# RP2350_MCU.net
KiCad netlist of a schematic drawn in Altium Designer
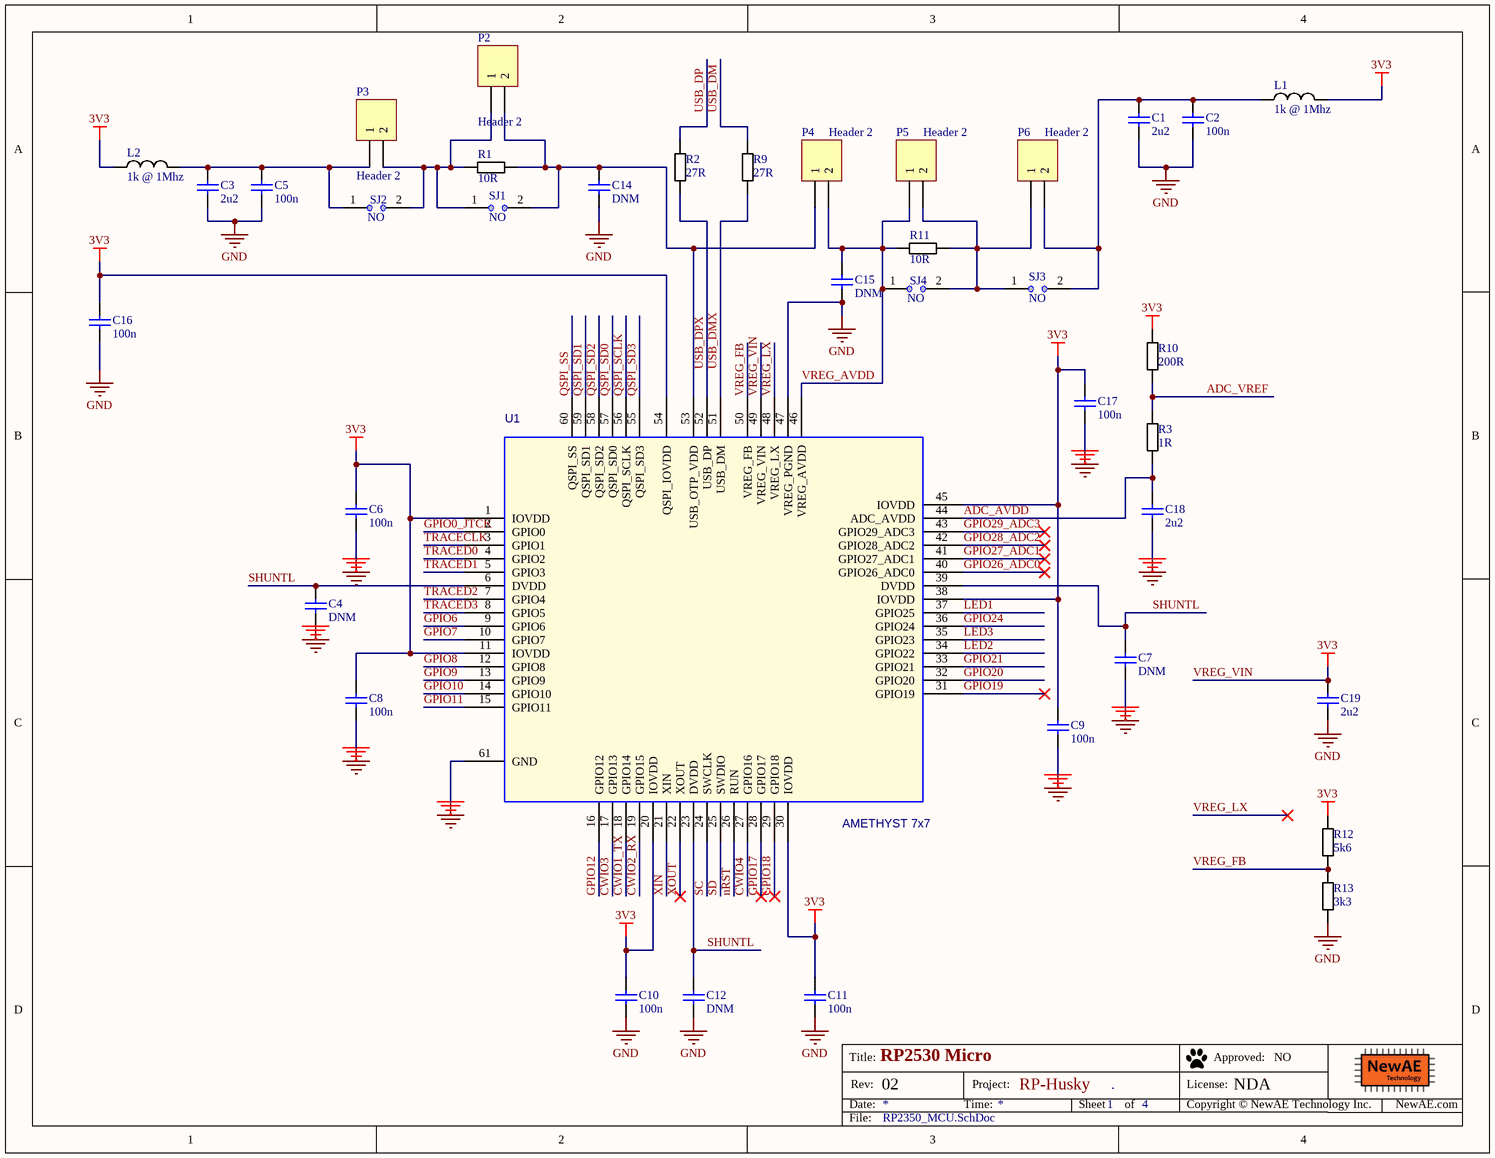
[diagram p0: RP2350_MCU.SchDoc]

(export (version "E")
  (design (tool "Eeschema 10.0.6"))
  (components
    (comp (ref "C1")
      (value "2u2")
      (footprint "CAPC0603_M")
      (description "2u2, 0603")
      (fields (field (name "PART NUMBER") "CCHIP-2u2-0603"))
      (libsource (lib "NewAE_AltiumLib") (part "CAP"))
    )
    (comp (ref "C2")
      (value "100n")
      (footprint "CAPC0402_M")
      (description "100n, 0402")
      (fields (field (name "PART NUMBER") "CCHIP-100n-0402"))
      (libsource (lib "NewAE_AltiumLib") (part "CAP"))
    )
    (comp (ref "C3")
      (value "2u2")
      (footprint "CAPC0603_M")
      (description "2u2, 0603")
      (fields (field (name "PART NUMBER") "CCHIP-2u2-0603"))
      (libsource (lib "NewAE_AltiumLib") (part "CAP"))
    )
    (comp (ref "C4")
      (value "DNM")
      (footprint "CAPC0603_M")
      (description "DNM, 0603")
      (fields (field (name "PART NUMBER") "CCHIP-DNM-0603"))
      (libsource (lib "NewAE_AltiumLib") (part "CAP"))
    )
    (comp (ref "C5")
      (value "100n")
      (footprint "CAPC0402_M")
      (description "100n, 0402")
      (fields (field (name "PART NUMBER") "CCHIP-100n-0402"))
      (libsource (lib "NewAE_AltiumLib") (part "CAP"))
    )
    (comp (ref "C6")
      (value "100n")
      (footprint "CAPC0402_M")
      (description "100n, 0402")
      (fields (field (name "PART NUMBER") "CCHIP-100n-0402"))
      (libsource (lib "NewAE_AltiumLib") (part "CAP"))
    )
    (comp (ref "C7")
      (value "DNM")
      (footprint "CAPC0603_M")
      (description "DNM, 0603")
      (fields (field (name "PART NUMBER") "CCHIP-DNM-0603"))
      (libsource (lib "NewAE_AltiumLib") (part "CAP"))
    )
    (comp (ref "C8")
      (value "100n")
      (footprint "CAPC0402_M")
      (description "100n, 0402")
      (fields (field (name "PART NUMBER") "CCHIP-100n-0402"))
      (libsource (lib "NewAE_AltiumLib") (part "CAP"))
    )
    (comp (ref "C9")
      (value "100n")
      (footprint "CAPC0402_M")
      (description "100n, 0402")
      (fields (field (name "PART NUMBER") "CCHIP-100n-0402"))
      (libsource (lib "NewAE_AltiumLib") (part "CAP"))
    )
    (comp (ref "C10")
      (value "100n")
      (footprint "CAPC0402_M")
      (description "100n, 0402")
      (fields (field (name "PART NUMBER") "CCHIP-100n-0402"))
      (libsource (lib "NewAE_AltiumLib") (part "CAP"))
    )
    (comp (ref "C11")
      (value "100n")
      (footprint "CAPC0402_M")
      (description "100n, 0402")
      (fields (field (name "PART NUMBER") "CCHIP-100n-0402"))
      (libsource (lib "NewAE_AltiumLib") (part "CAP"))
    )
    (comp (ref "C12")
      (value "DNM")
      (footprint "CAPC0603_M")
      (description "DNM, 0603")
      (fields (field (name "PART NUMBER") "CCHIP-DNM-0603"))
      (libsource (lib "NewAE_AltiumLib") (part "CAP"))
    )
    (comp (ref "C14")
      (value "DNM")
      (footprint "CAPC0603_M")
      (description "DNM, 0603")
      (fields (field (name "PART NUMBER") "CCHIP-DNM-0603"))
      (libsource (lib "NewAE_AltiumLib") (part "CAP"))
    )
    (comp (ref "C15")
      (value "DNM")
      (footprint "CAPC0603_M")
      (description "DNM, 0603")
      (fields (field (name "PART NUMBER") "CCHIP-DNM-0603"))
      (libsource (lib "NewAE_AltiumLib") (part "CAP"))
    )
    (comp (ref "C16")
      (value "100n")
      (footprint "CAPC0402_M")
      (description "100n, 0402")
      (fields (field (name "PART NUMBER") "CCHIP-100n-0402"))
      (libsource (lib "NewAE_AltiumLib") (part "CAP"))
    )
    (comp (ref "C17")
      (value "100n")
      (footprint "CAPC0402_M")
      (description "100n, 0402")
      (fields (field (name "PART NUMBER") "CCHIP-100n-0402"))
      (libsource (lib "NewAE_AltiumLib") (part "CAP"))
    )
    (comp (ref "C18")
      (value "2u2")
      (footprint "CAPC0603_M")
      (description "2u2, 0603")
      (fields (field (name "PART NUMBER") "CCHIP-2u2-0603"))
      (libsource (lib "NewAE_AltiumLib") (part "CAP"))
    )
    (comp (ref "C19")
      (value "2u2")
      (footprint "CAPC0603_M")
      (description "2u2, 0603")
      (fields (field (name "PART NUMBER") "CCHIP-2u2-0603"))
      (libsource (lib "NewAE_AltiumLib") (part "CAP"))
    )
    (comp (ref "L1")
      (value "1k @ 1Mhz")
      (footprint "IND_0603")
      (description "Ferrite Beads HI CUR CHIP BD 0603 1000OHMS 25%")
      (fields (field (name "PART NUMBER") "FBCHIP-1k-0603"))
      (libsource (lib "NewAE_AltiumLib") (part "IND"))
    )
    (comp (ref "L2")
      (value "1k @ 1Mhz")
      (footprint "IND_0603")
      (description "Ferrite Beads HI CUR CHIP BD 0603 1000OHMS 25%")
      (fields (field (name "PART NUMBER") "FBCHIP-1k-0603"))
      (libsource (lib "NewAE_AltiumLib") (part "IND"))
    )
    (comp (ref "P2")
      (value "Header 2")
      (footprint "HDR1X2")
      (description "Header, 2-Pin")
      (fields (field (name "PUBLISHER") "Altium Limited"))
      (libsource (lib "Miscellaneous Connectors") (part "Header 2"))
    )
    (comp (ref "P3")
      (value "Header 2")
      (footprint "HDR1X2")
      (description "Header, 2-Pin")
      (fields (field (name "PUBLISHER") "Altium Limited"))
      (libsource (lib "Miscellaneous Connectors") (part "Header 2"))
    )
    (comp (ref "P4")
      (value "Header 2")
      (footprint "HDR1X2")
      (description "Header, 2-Pin")
      (fields (field (name "PUBLISHER") "Altium Limited"))
      (libsource (lib "Miscellaneous Connectors") (part "Header 2"))
    )
    (comp (ref "P5")
      (value "Header 2")
      (footprint "HDR1X2")
      (description "Header, 2-Pin")
      (fields (field (name "PUBLISHER") "Altium Limited"))
      (libsource (lib "Miscellaneous Connectors") (part "Header 2"))
    )
    (comp (ref "P6")
      (value "Header 2")
      (footprint "HDR1X2")
      (description "Header, 2-Pin")
      (fields (field (name "PUBLISHER") "Altium Limited"))
      (libsource (lib "Miscellaneous Connectors") (part "Header 2"))
    )
    (comp (ref "R1")
      (value "10R")
      (footprint "RESC1608X55N")
      (description "10R res, 0603, 1%, 1/10W")
      (fields (field (name "PART NUMBER") "RCHIP-10R-0603") (field (name "TOLERANCE") "1%"))
      (libsource (lib "NewAE_AltiumLib") (part "RES-EU"))
    )
    (comp (ref "R2")
      (value "27R")
      (footprint "RESC1608X55N")
      (description "27R res, 0603, 1%, 1/10W")
      (fields (field (name "PART NUMBER") "RCHIP-27R-0603") (field (name "TOLERANCE") "1%"))
      (libsource (lib "") (part "RES-EU_1"))
    )
    (comp (ref "R3")
      (value "1R")
      (footprint "RESC1608X55N")
      (description "1R res, 0603, 1%, 1/10W")
      (fields (field (name "PART NUMBER") "RCHIP-10R-0603") (field (name "TOLERANCE") "1%"))
      (libsource (lib "") (part "RES-EU_1"))
    )
    (comp (ref "R9")
      (value "27R")
      (footprint "RESC1608X55N")
      (description "27R res, 0603, 1%, 1/10W")
      (fields (field (name "PART NUMBER") "RCHIP-27R-0603") (field (name "TOLERANCE") "1%"))
      (libsource (lib "") (part "RES-EU_1"))
    )
    (comp (ref "R10")
      (value "200R")
      (footprint "RESC1608X55N")
      (description "200R res, 0603, 1%, 1/10W")
      (fields (field (name "PART NUMBER") "RCHIP-200R-0603") (field (name "TOLERANCE") "1%"))
      (libsource (lib "") (part "RES-EU_2"))
    )
    (comp (ref "R11")
      (value "10R")
      (footprint "RESC1608X55N")
      (description "10R res, 0603, 1%, 1/10W")
      (fields (field (name "PART NUMBER") "RCHIP-10R-0603") (field (name "TOLERANCE") "1%"))
      (libsource (lib "NewAE_AltiumLib") (part "RES-EU"))
    )
    (comp (ref "R12")
      (value "5k6")
      (footprint "RESC1608X55N")
      (description "5k6 res, 0603, 1%, 1/10W")
      (fields (field (name "PART NUMBER") "RCHIP-5K6-0603") (field (name "TOLERANCE") "1%"))
      (libsource (lib "") (part "RES-EU_2"))
    )
    (comp (ref "R13")
      (value "3k3")
      (footprint "RESC1608X55N")
      (description "3k3 res, 0603, 1%, 1/10W")
      (fields (field (name "PART NUMBER") "RCHIP-3K3-0603") (field (name "TOLERANCE") "1%"))
      (libsource (lib "") (part "RES-EU_2"))
    )
    (comp (ref "SJ1")
      (value "NO")
      (footprint "SJ_2S_NO")
      (description "Solder Jumper, NO")
      (fields (field (name "PART NUMBER") "SJ_2S_NO"))
      (libsource (lib "NewAE_AltiumLib") (part "SJ_2S_NO"))
    )
    (comp (ref "SJ2")
      (value "NO")
      (footprint "SJ_2S_NO")
      (description "Solder Jumper, NO")
      (fields (field (name "PART NUMBER") "SJ_2S_NO"))
      (libsource (lib "NewAE_AltiumLib") (part "SJ_2S_NO"))
    )
    (comp (ref "SJ3")
      (value "NO")
      (footprint "SJ_2S_NO")
      (description "Solder Jumper, NO")
      (fields (field (name "PART NUMBER") "SJ_2S_NO"))
      (libsource (lib "NewAE_AltiumLib") (part "SJ_2S_NO"))
    )
    (comp (ref "SJ4")
      (value "NO")
      (footprint "SJ_2S_NO")
      (description "Solder Jumper, NO")
      (fields (field (name "PART NUMBER") "SJ_2S_NO"))
      (libsource (lib "NewAE_AltiumLib") (part "SJ_2S_NO"))
    )
    (comp (ref "U1")
      (value "AMETHYST 7x7")
      (footprint "QFN60P700X700X85_HS-61M")
      (libsource (lib "*") (part "RPI_AMETHYST-7X7"))
    )
  )
  (nets
    (net (code "1") (name "/ADC_AVDD") (class "Default")
      (node (ref "C18") (pin "1") (pinfunction "1_1") (pintype "passive"))
      (node (ref "R3") (pin "1") (pinfunction "1_1") (pintype "passive"))
      (node (ref "U1") (pin "44") (pinfunction "ADC_AVDD_44") (pintype "power_in"))
    )
    (net (code "2") (name "/ADC_VREF") (class "Default")
      (node (ref "R10") (pin "2") (pinfunction "2_2") (pintype "passive"))
      (node (ref "R3") (pin "2") (pinfunction "2_2") (pintype "passive"))
    )
    (net (code "3") (name "/CWIO1_TX") (class "Default")
      (node (ref "U1") (pin "18") (pinfunction "GPIO14_18") (pintype "passive"))
    )
    (net (code "4") (name "/CWIO2_RX") (class "Default")
      (node (ref "U1") (pin "19") (pinfunction "GPIO15_19") (pintype "passive"))
    )
    (net (code "5") (name "/CWIO3") (class "Default")
      (node (ref "U1") (pin "17") (pinfunction "GPIO13_17") (pintype "passive"))
    )
    (net (code "6") (name "/CWIO4") (class "Default")
      (node (ref "U1") (pin "27") (pinfunction "GPIO16_27") (pintype "passive"))
    )
    (net (code "7") (name "/GPIO0_JTCK") (class "Default")
      (node (ref "U1") (pin "2") (pinfunction "GPIO0_2") (pintype "passive"))
    )
    (net (code "8") (name "/GPIO6") (class "Default")
      (node (ref "U1") (pin "9") (pinfunction "GPIO6_9") (pintype "passive"))
    )
    (net (code "9") (name "/GPIO7") (class "Default")
      (node (ref "U1") (pin "10") (pinfunction "GPIO7_10") (pintype "passive"))
    )
    (net (code "10") (name "/GPIO8") (class "Default")
      (node (ref "U1") (pin "12") (pinfunction "GPIO8_12") (pintype "passive"))
    )
    (net (code "11") (name "/GPIO9") (class "Default")
      (node (ref "U1") (pin "13") (pinfunction "GPIO9_13") (pintype "passive"))
    )
    (net (code "12") (name "/GPIO10") (class "Default")
      (node (ref "U1") (pin "14") (pinfunction "GPIO10_14") (pintype "passive"))
    )
    (net (code "13") (name "/GPIO11") (class "Default")
      (node (ref "U1") (pin "15") (pinfunction "GPIO11_15") (pintype "passive"))
    )
    (net (code "14") (name "/GPIO12") (class "Default")
      (node (ref "U1") (pin "16") (pinfunction "GPIO12_16") (pintype "passive"))
    )
    (net (code "15") (name "/GPIO17") (class "Default")
      (node (ref "U1") (pin "28") (pinfunction "GPIO17_28") (pintype "passive+no_connect"))
    )
    (net (code "16") (name "/GPIO18") (class "Default")
      (node (ref "U1") (pin "29") (pinfunction "GPIO18_29") (pintype "passive+no_connect"))
    )
    (net (code "17") (name "/GPIO19") (class "Default")
      (node (ref "U1") (pin "31") (pinfunction "GPIO19_31") (pintype "passive+no_connect"))
    )
    (net (code "18") (name "/GPIO20") (class "Default")
      (node (ref "U1") (pin "32") (pinfunction "GPIO20_32") (pintype "passive"))
    )
    (net (code "19") (name "/GPIO21") (class "Default")
      (node (ref "U1") (pin "33") (pinfunction "GPIO21_33") (pintype "passive"))
    )
    (net (code "20") (name "/GPIO24") (class "Default")
      (node (ref "U1") (pin "36") (pinfunction "GPIO24_36") (pintype "passive"))
    )
    (net (code "21") (name "/GPIO26_ADC0") (class "Default")
      (node (ref "U1") (pin "40") (pinfunction "GPIO26_ADC0_40") (pintype "passive+no_connect"))
    )
    (net (code "22") (name "/GPIO27_ADC1") (class "Default")
      (node (ref "U1") (pin "41") (pinfunction "GPIO27_ADC1_41") (pintype "passive+no_connect"))
    )
    (net (code "23") (name "/GPIO28_ADC2") (class "Default")
      (node (ref "U1") (pin "42") (pinfunction "GPIO28_ADC2_42") (pintype "passive+no_connect"))
    )
    (net (code "24") (name "/GPIO29_ADC3") (class "Default")
      (node (ref "U1") (pin "43") (pinfunction "GPIO29_ADC3_43") (pintype "passive+no_connect"))
    )
    (net (code "25") (name "/LED1") (class "Default")
      (node (ref "U1") (pin "37") (pinfunction "GPIO25_37") (pintype "passive"))
    )
    (net (code "26") (name "/LED2") (class "Default")
      (node (ref "U1") (pin "34") (pinfunction "GPIO22_34") (pintype "passive"))
    )
    (net (code "27") (name "/LED3") (class "Default")
      (node (ref "U1") (pin "35") (pinfunction "GPIO23_35") (pintype "passive"))
    )
    (net (code "28") (name "/QSPI_SCLK") (class "Default")
      (node (ref "U1") (pin "56") (pinfunction "QSPI_SCLK_56") (pintype "passive"))
    )
    (net (code "29") (name "/QSPI_SD0") (class "Default")
      (node (ref "U1") (pin "57") (pinfunction "QSPI_SD0_57") (pintype "passive"))
    )
    (net (code "30") (name "/QSPI_SD1") (class "Default")
      (node (ref "U1") (pin "59") (pinfunction "QSPI_SD1_59") (pintype "passive"))
    )
    (net (code "31") (name "/QSPI_SD2") (class "Default")
      (node (ref "U1") (pin "58") (pinfunction "QSPI_SD2_58") (pintype "passive"))
    )
    (net (code "32") (name "/QSPI_SD3") (class "Default")
      (node (ref "U1") (pin "55") (pinfunction "QSPI_SD3_55") (pintype "passive"))
    )
    (net (code "33") (name "/QSPI_SS") (class "Default")
      (node (ref "U1") (pin "60") (pinfunction "QSPI_SS_60") (pintype "passive"))
    )
    (net (code "34") (name "/SC") (class "Default")
      (node (ref "U1") (pin "24") (pinfunction "SWCLK_24") (pintype "passive"))
    )
    (net (code "35") (name "/SD") (class "Default")
      (node (ref "U1") (pin "25") (pinfunction "SWDIO_25") (pintype "passive"))
    )
    (net (code "36") (name "/SHUNTL") (class "Default")
      (node (ref "C12") (pin "1") (pinfunction "1_1") (pintype "passive"))
      (node (ref "C4") (pin "1") (pinfunction "1_1") (pintype "passive"))
      (node (ref "C7") (pin "1") (pinfunction "1_1") (pintype "passive"))
      (node (ref "U1") (pin "23") (pinfunction "DVDD_23") (pintype "power_in"))
      (node (ref "U1") (pin "39") (pinfunction "DVDD_39") (pintype "power_in"))
      (node (ref "U1") (pin "6") (pinfunction "DVDD_6") (pintype "power_in"))
    )
    (net (code "37") (name "/TRACECLK") (class "Default")
      (node (ref "U1") (pin "3") (pinfunction "GPIO1_3") (pintype "passive"))
    )
    (net (code "38") (name "/TRACED0") (class "Default")
      (node (ref "U1") (pin "4") (pinfunction "GPIO2_4") (pintype "passive"))
    )
    (net (code "39") (name "/TRACED1") (class "Default")
      (node (ref "U1") (pin "5") (pinfunction "GPIO3_5") (pintype "passive"))
    )
    (net (code "40") (name "/TRACED2") (class "Default")
      (node (ref "U1") (pin "7") (pinfunction "GPIO4_7") (pintype "passive"))
    )
    (net (code "41") (name "/TRACED3") (class "Default")
      (node (ref "U1") (pin "8") (pinfunction "GPIO5_8") (pintype "passive"))
    )
    (net (code "42") (name "/USB_DM") (class "Default")
      (node (ref "R9") (pin "2") (pinfunction "2_2") (pintype "passive"))
    )
    (net (code "43") (name "/USB_DMX") (class "Default")
      (node (ref "R9") (pin "1") (pinfunction "1_1") (pintype "passive"))
      (node (ref "U1") (pin "51") (pinfunction "USB_DM_51") (pintype "passive"))
    )
    (net (code "44") (name "/USB_DP") (class "Default")
      (node (ref "R2") (pin "2") (pinfunction "2_2") (pintype "passive"))
    )
    (net (code "45") (name "/USB_DPX") (class "Default")
      (node (ref "R2") (pin "1") (pinfunction "1_1") (pintype "passive"))
      (node (ref "U1") (pin "52") (pinfunction "USB_DP_52") (pintype "passive"))
    )
    (net (code "46") (name "/VREG_AVDD") (class "Default")
      (node (ref "C15") (pin "1") (pinfunction "1_1") (pintype "passive"))
      (node (ref "P4") (pin "2") (pinfunction "2_2") (pintype "passive"))
      (node (ref "P5") (pin "1") (pinfunction "1_1") (pintype "passive"))
      (node (ref "R11") (pin "1") (pinfunction "1_1") (pintype "passive"))
      (node (ref "SJ4") (pin "1") (pinfunction "1_1") (pintype "passive"))
      (node (ref "U1") (pin "46") (pinfunction "VREG_AVDD_46") (pintype "power_in"))
    )
    (net (code "47") (name "/VREG_FB") (class "Default")
      (node (ref "R12") (pin "2") (pinfunction "2_2") (pintype "passive"))
      (node (ref "R13") (pin "1") (pinfunction "1_1") (pintype "passive"))
      (node (ref "U1") (pin "50") (pinfunction "VREG_FB_50") (pintype "passive"))
    )
    (net (code "48") (name "/VREG_LX") (class "Default")
      (node (ref "U1") (pin "48") (pinfunction "VREG_LX_48") (pintype "passive+no_connect"))
    )
    (net (code "49") (name "/XIN") (class "Default")
      (node (ref "U1") (pin "21") (pinfunction "XIN_21") (pintype "passive"))
    )
    (net (code "50") (name "/XOUT") (class "Default")
      (node (ref "U1") (pin "22") (pinfunction "XOUT_22") (pintype "passive+no_connect"))
    )
    (net (code "51") (name "/nRST") (class "Default")
      (node (ref "U1") (pin "26") (pinfunction "RUN_26") (pintype "passive"))
    )
    (net (code "52") (name "3V3") (class "Default")
      (node (ref "C10") (pin "1") (pinfunction "1_1") (pintype "passive"))
      (node (ref "C11") (pin "1") (pinfunction "1_1") (pintype "passive"))
      (node (ref "C16") (pin "1") (pinfunction "1_1") (pintype "passive"))
      (node (ref "C17") (pin "1") (pinfunction "1_1") (pintype "passive"))
      (node (ref "C19") (pin "1") (pinfunction "1_1") (pintype "passive"))
      (node (ref "C6") (pin "1") (pinfunction "1_1") (pintype "passive"))
      (node (ref "C8") (pin "1") (pinfunction "1_1") (pintype "passive"))
      (node (ref "C9") (pin "1") (pinfunction "1_1") (pintype "passive"))
      (node (ref "L1") (pin "2") (pinfunction "2_2") (pintype "passive"))
      (node (ref "L2") (pin "1") (pinfunction "1_1") (pintype "passive"))
      (node (ref "R10") (pin "1") (pinfunction "1_1") (pintype "passive"))
      (node (ref "R12") (pin "1") (pinfunction "1_1") (pintype "passive"))
      (node (ref "U1") (pin "1") (pinfunction "IOVDD_1") (pintype "power_in"))
      (node (ref "U1") (pin "11") (pinfunction "IOVDD_11") (pintype "power_in"))
      (node (ref "U1") (pin "20") (pinfunction "IOVDD_20") (pintype "power_in"))
      (node (ref "U1") (pin "30") (pinfunction "IOVDD_30") (pintype "power_in"))
      (node (ref "U1") (pin "38") (pinfunction "IOVDD_38") (pintype "power_in"))
      (node (ref "U1") (pin "45") (pinfunction "IOVDD_45") (pintype "power_in"))
      (node (ref "U1") (pin "49") (pinfunction "VREG_VIN_49") (pintype "power_in"))
      (node (ref "U1") (pin "54") (pinfunction "QSPI_IOVDD_54") (pintype "power_in"))
    )
    (net (code "53") (name "GND") (class "Default")
      (node (ref "C1") (pin "2") (pinfunction "2_2") (pintype "passive"))
      (node (ref "C10") (pin "2") (pinfunction "2_2") (pintype "passive"))
      (node (ref "C11") (pin "2") (pinfunction "2_2") (pintype "passive"))
      (node (ref "C12") (pin "2") (pinfunction "2_2") (pintype "passive"))
      (node (ref "C14") (pin "2") (pinfunction "2_2") (pintype "passive"))
      (node (ref "C15") (pin "2") (pinfunction "2_2") (pintype "passive"))
      (node (ref "C16") (pin "2") (pinfunction "2_2") (pintype "passive"))
      (node (ref "C17") (pin "2") (pinfunction "2_2") (pintype "passive"))
      (node (ref "C18") (pin "2") (pinfunction "2_2") (pintype "passive"))
      (node (ref "C19") (pin "2") (pinfunction "2_2") (pintype "passive"))
      (node (ref "C2") (pin "2") (pinfunction "2_2") (pintype "passive"))
      (node (ref "C3") (pin "2") (pinfunction "2_2") (pintype "passive"))
      (node (ref "C4") (pin "2") (pinfunction "2_2") (pintype "passive"))
      (node (ref "C5") (pin "2") (pinfunction "2_2") (pintype "passive"))
      (node (ref "C6") (pin "2") (pinfunction "2_2") (pintype "passive"))
      (node (ref "C7") (pin "2") (pinfunction "2_2") (pintype "passive"))
      (node (ref "C8") (pin "2") (pinfunction "2_2") (pintype "passive"))
      (node (ref "C9") (pin "2") (pinfunction "2_2") (pintype "passive"))
      (node (ref "R13") (pin "2") (pinfunction "2_2") (pintype "passive"))
      (node (ref "U1") (pin "47") (pinfunction "VREG_PGND_47") (pintype "passive"))
      (node (ref "U1") (pin "61") (pinfunction "GND_61") (pintype "power_in"))
    )
    (net (code "54") (name "Net-(C1-Pad1)") (class "Default")
      (node (ref "C1") (pin "1") (pinfunction "1_1") (pintype "passive"))
      (node (ref "C2") (pin "1") (pinfunction "1_1") (pintype "passive"))
      (node (ref "L1") (pin "1") (pinfunction "1_1") (pintype "passive"))
      (node (ref "P6") (pin "2") (pinfunction "2_2") (pintype "passive"))
      (node (ref "SJ3") (pin "2") (pinfunction "2_2") (pintype "passive"))
    )
    (net (code "55") (name "Net-(C3-Pad1)") (class "Default")
      (node (ref "C3") (pin "1") (pinfunction "1_1") (pintype "passive"))
      (node (ref "C5") (pin "1") (pinfunction "1_1") (pintype "passive"))
      (node (ref "L2") (pin "2") (pinfunction "2_2") (pintype "passive"))
      (node (ref "P3") (pin "1") (pinfunction "1_1") (pintype "passive"))
      (node (ref "SJ2") (pin "1") (pinfunction "1_1") (pintype "passive"))
    )
    (net (code "56") (name "Net-(P2-Pad1)") (class "Default")
      (node (ref "P2") (pin "1") (pinfunction "1_1") (pintype "passive"))
      (node (ref "P3") (pin "2") (pinfunction "2_2") (pintype "passive"))
      (node (ref "R1") (pin "1") (pinfunction "1_1") (pintype "passive"))
      (node (ref "SJ1") (pin "1") (pinfunction "1_1") (pintype "passive"))
      (node (ref "SJ2") (pin "2") (pinfunction "2_2") (pintype "passive"))
    )
    (net (code "57") (name "Net-(P5-Pad2)") (class "Default")
      (node (ref "P5") (pin "2") (pinfunction "2_2") (pintype "passive"))
      (node (ref "P6") (pin "1") (pinfunction "1_1") (pintype "passive"))
      (node (ref "R11") (pin "2") (pinfunction "2_2") (pintype "passive"))
      (node (ref "SJ3") (pin "1") (pinfunction "1_1") (pintype "passive"))
      (node (ref "SJ4") (pin "2") (pinfunction "2_2") (pintype "passive"))
    )
    (net (code "58") (name "Net-(U1-USB_OTP_VDD)") (class "Default")
      (node (ref "C14") (pin "1") (pinfunction "1_1") (pintype "passive"))
      (node (ref "P2") (pin "2") (pinfunction "2_2") (pintype "passive"))
      (node (ref "P4") (pin "1") (pinfunction "1_1") (pintype "passive"))
      (node (ref "R1") (pin "2") (pinfunction "2_2") (pintype "passive"))
      (node (ref "SJ1") (pin "2") (pinfunction "2_2") (pintype "passive"))
      (node (ref "U1") (pin "53") (pinfunction "USB_OTP_VDD_53") (pintype "power_in"))
    )
  )
)
